# MRF39.net
KiCad netlist of a schematic drawn in EAGLE
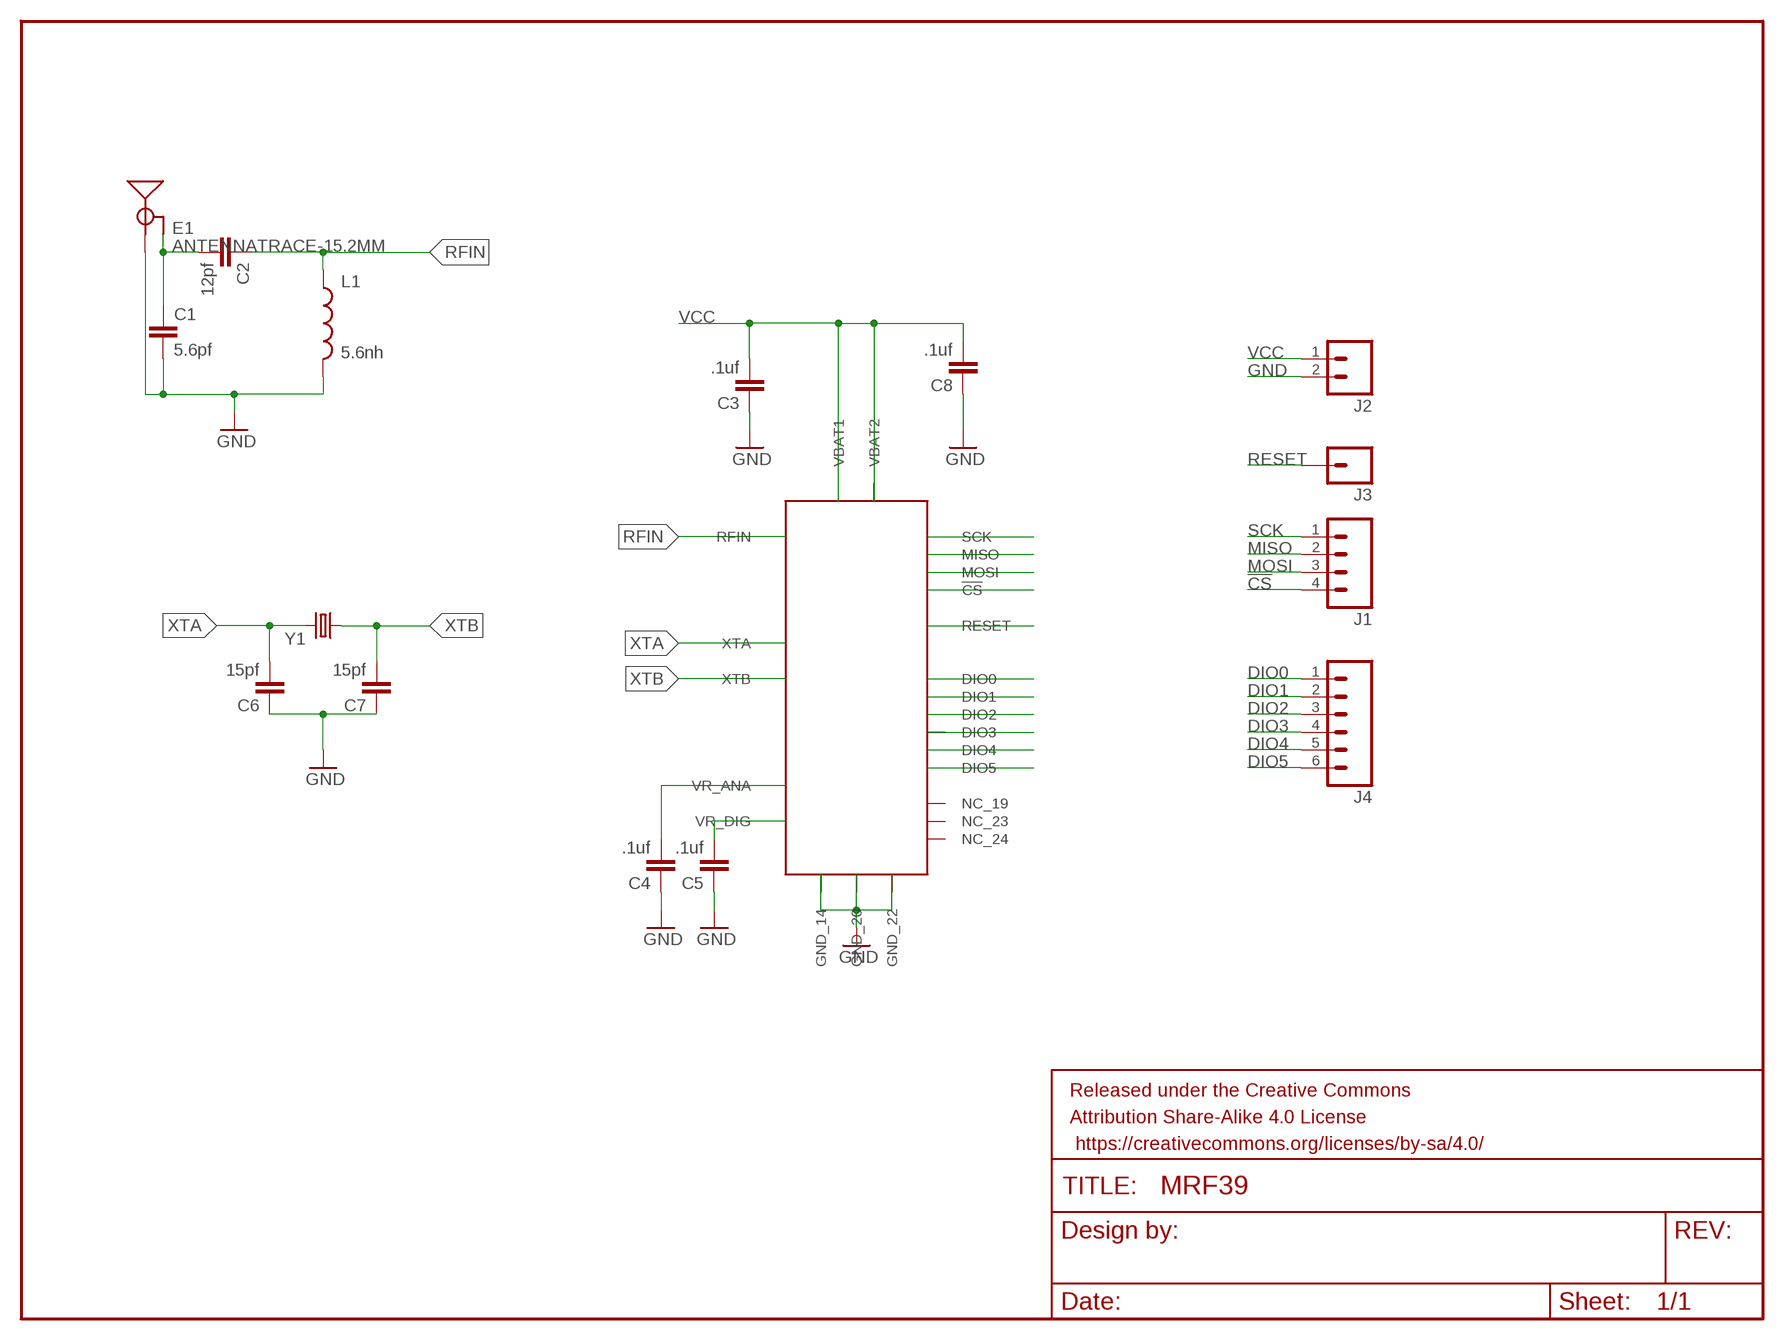
[diagram p0: schematic, sheet 1]

(export (version "E")
  (design (tool "Eeschema 10.0.6"))
  (components
    (comp (ref "C1")
      (value "5.6pf")
      (footprint "eagle-import:0603-CAP")
      (libsource (lib "eagle-import") (part "CAP0603-CAP"))
    )
    (comp (ref "C2")
      (value "12pf")
      (footprint "eagle-import:0603-CAP")
      (libsource (lib "eagle-import") (part "CAP0603-CAP"))
    )
    (comp (ref "C3")
      (value ".1uf")
      (footprint "eagle-import:0603-CAP")
      (libsource (lib "eagle-import") (part "CAP0603-CAP"))
    )
    (comp (ref "C4")
      (value ".1uf")
      (footprint "eagle-import:0603-CAP")
      (libsource (lib "eagle-import") (part "CAP0603-CAP"))
    )
    (comp (ref "C5")
      (value ".1uf")
      (footprint "eagle-import:0603-CAP")
      (libsource (lib "eagle-import") (part "CAP0603-CAP"))
    )
    (comp (ref "C6")
      (value "15pf")
      (footprint "eagle-import:0603-CAP")
      (libsource (lib "eagle-import") (part "CAP0603-CAP"))
    )
    (comp (ref "C7")
      (value "15pf")
      (footprint "eagle-import:0603-CAP")
      (libsource (lib "eagle-import") (part "CAP0603-CAP"))
    )
    (comp (ref "C8")
      (value ".1uf")
      (footprint "eagle-import:0603-CAP")
      (libsource (lib "eagle-import") (part "CAP0603-CAP"))
    )
    (comp (ref "E1")
      (value "ANTENNATRACE-15.2MM")
      (footprint "eagle-import:TRACE_ANTENNA_2.4GHZ_15.2MM")
      (libsource (lib "eagle-import") (part "ANTENNATRACE-15.2MM"))
    )
    (comp (ref "FRAME1")
      (value "FRAME-LETTERNO_PACKAGE")
      (footprint "eagle-import:DUMMY")
      (fields (field (name "DESIGNER") "Nobody"))
      (libsource (lib "eagle-import") (part "FRAME-LETTERNO_PACKAGE"))
    )
    (comp (ref "J1")
      (value "M04PTH")
      (footprint "eagle-import:1X04")
      (libsource (lib "eagle-import") (part "M04PTH"))
    )
    (comp (ref "J2")
      (value "M02PTH")
      (footprint "eagle-import:1X02")
      (libsource (lib "eagle-import") (part "M02PTH"))
    )
    (comp (ref "J3")
      (value "M01PTH")
      (footprint "eagle-import:1X01")
      (libsource (lib "eagle-import") (part "M01PTH"))
    )
    (comp (ref "J4")
      (value "M06SILK_FEMALE_PTH")
      (footprint "eagle-import:1X06")
      (libsource (lib "eagle-import") (part "M06SILK_FEMALE_PTH"))
    )
    (comp (ref "L1")
      (value "5.6nh")
      (footprint "eagle-import:0805")
      (libsource (lib "eagle-import") (part "INDUCTOR0805"))
    )
    (comp (ref "U1")
      (value "MRF39RATQFN24")
      (footprint "eagle-import:QFN24-5X5X1.0")
      (libsource (lib "eagle-import") (part "MRF39RATQFN24"))
    )
    (comp (ref "Y1")
      (value "CRYSTALSMD")
      (footprint "eagle-import:HC49UP")
      (libsource (lib "eagle-import") (part "CRYSTALSMD"))
    )
  )
  (nets
    (net (code "1") (name "/DIO0") (class "Default")
      (node (ref "J4") (pin "1") (pinfunction "1_1") (pintype "passive"))
      (node (ref "U1") (pin "7") (pinfunction "DIO0_7") (pintype "bidirectional"))
    )
    (net (code "2") (name "/DIO1") (class "Default")
      (node (ref "J4") (pin "2") (pinfunction "2_2") (pintype "passive"))
      (node (ref "U1") (pin "8") (pinfunction "DIO1_8") (pintype "bidirectional"))
    )
    (net (code "3") (name "/DIO2") (class "Default")
      (node (ref "J4") (pin "3") (pinfunction "3_3") (pintype "passive"))
      (node (ref "U1") (pin "9") (pinfunction "DIO2_9") (pintype "bidirectional"))
    )
    (net (code "4") (name "/DIO3") (class "Default")
      (node (ref "J4") (pin "4") (pinfunction "4_4") (pintype "passive"))
      (node (ref "U1") (pin "10") (pinfunction "DIO3_10") (pintype "bidirectional"))
    )
    (net (code "5") (name "/DIO4") (class "Default")
      (node (ref "J4") (pin "5") (pinfunction "5_5") (pintype "passive"))
      (node (ref "U1") (pin "11") (pinfunction "DIO4_11") (pintype "bidirectional"))
    )
    (net (code "6") (name "/DIO5") (class "Default")
      (node (ref "J4") (pin "6") (pinfunction "6_6") (pintype "passive"))
      (node (ref "U1") (pin "12") (pinfunction "DIO5_12") (pintype "bidirectional"))
    )
    (net (code "7") (name "/MISO") (class "Default")
      (node (ref "J1") (pin "2") (pinfunction "2_2") (pintype "passive"))
      (node (ref "U1") (pin "16") (pinfunction "MISO_16") (pintype "bidirectional"))
    )
    (net (code "8") (name "/MOSI") (class "Default")
      (node (ref "J1") (pin "3") (pinfunction "3_3") (pintype "passive"))
      (node (ref "U1") (pin "17") (pinfunction "MOSI_17") (pintype "bidirectional"))
    )
    (net (code "9") (name "/RESET") (class "Default")
      (node (ref "J3") (pin "1") (pinfunction "1_1") (pintype "passive"))
      (node (ref "U1") (pin "6") (pinfunction "RESET_6") (pintype "bidirectional"))
    )
    (net (code "10") (name "/SCK") (class "Default")
      (node (ref "J1") (pin "1") (pinfunction "1_1") (pintype "passive"))
      (node (ref "U1") (pin "15") (pinfunction "SCK_15") (pintype "bidirectional"))
    )
    (net (code "11") (name "/VCC") (class "Default")
      (node (ref "C3") (pin "2") (pinfunction "2_2") (pintype "passive"))
      (node (ref "C8") (pin "2") (pinfunction "2_2") (pintype "passive"))
      (node (ref "J2") (pin "1") (pinfunction "1_1") (pintype "passive"))
      (node (ref "U1") (pin "1") (pinfunction "VBAT1_1") (pintype "bidirectional"))
      (node (ref "U1") (pin "13") (pinfunction "VBAT2_13") (pintype "bidirectional"))
    )
    (net (code "12") (name "/~{CS}") (class "Default")
      (node (ref "J1") (pin "4") (pinfunction "4_4") (pintype "passive"))
      (node (ref "U1") (pin "18") (pinfunction "~{CS}_18") (pintype "bidirectional"))
    )
    (net (code "13") (name "GND") (class "Default")
      (node (ref "C1") (pin "2") (pinfunction "2_2") (pintype "passive"))
      (node (ref "C3") (pin "1") (pinfunction "1_1") (pintype "passive"))
      (node (ref "C4") (pin "1") (pinfunction "1_1") (pintype "passive"))
      (node (ref "C5") (pin "1") (pinfunction "1_1") (pintype "passive"))
      (node (ref "C6") (pin "1") (pinfunction "1_1") (pintype "passive"))
      (node (ref "C7") (pin "1") (pinfunction "1_1") (pintype "passive"))
      (node (ref "C8") (pin "1") (pinfunction "1_1") (pintype "passive"))
      (node (ref "E1") (pin "ANT") (pinfunction "SIGNAL_ANT") (pintype "bidirectional"))
      (node (ref "J2") (pin "2") (pinfunction "2_2") (pintype "passive"))
      (node (ref "L1") (pin "2") (pinfunction "2_2") (pintype "passive"))
      (node (ref "U1") (pin "14") (pinfunction "GND_14_14") (pintype "power_in"))
      (node (ref "U1") (pin "20") (pinfunction "GND_20_20") (pintype "power_in"))
      (node (ref "U1") (pin "22") (pinfunction "GND_22_22") (pintype "power_in"))
    )
    (net (code "14") (name "Net-(C1-Pad1)") (class "Default")
      (node (ref "C1") (pin "1") (pinfunction "1_1") (pintype "passive"))
      (node (ref "C2") (pin "2") (pinfunction "2_2") (pintype "passive"))
      (node (ref "E1") (pin "GND") (pinfunction "GND_GND") (pintype "bidirectional"))
    )
    (net (code "15") (name "Net-(U1-VR_ANA)") (class "Default")
      (node (ref "C4") (pin "2") (pinfunction "2_2") (pintype "passive"))
      (node (ref "U1") (pin "2") (pinfunction "VR_ANA_2") (pintype "power_in"))
    )
    (net (code "16") (name "Net-(U1-VR_DIG)") (class "Default")
      (node (ref "C5") (pin "2") (pinfunction "2_2") (pintype "passive"))
      (node (ref "U1") (pin "3") (pinfunction "VR_DIG_3") (pintype "power_in"))
    )
    (net (code "17") (name "RFIN") (class "Default")
      (node (ref "C2") (pin "1") (pinfunction "1_1") (pintype "passive"))
      (node (ref "L1") (pin "1") (pinfunction "1_1") (pintype "passive"))
      (node (ref "U1") (pin "21") (pinfunction "RFIN_21") (pintype "output"))
    )
    (net (code "18") (name "XTA") (class "Default")
      (node (ref "C6") (pin "2") (pinfunction "2_2") (pintype "passive"))
      (node (ref "U1") (pin "4") (pinfunction "XTA_4") (pintype "power_in"))
      (node (ref "Y1") (pin "2") (pinfunction "2_2") (pintype "passive"))
    )
    (net (code "19") (name "XTB") (class "Default")
      (node (ref "C7") (pin "2") (pinfunction "2_2") (pintype "passive"))
      (node (ref "U1") (pin "5") (pinfunction "XTB_5") (pintype "power_in"))
      (node (ref "Y1") (pin "1") (pinfunction "1_1") (pintype "passive"))
    )
    (net (code "20") (name "unconnected-(U1-NC_19-Pad19)") (class "Default")
      (node (ref "U1") (pin "19") (pinfunction "NC_19_19") (pintype "no_connect"))
    )
    (net (code "21") (name "unconnected-(U1-NC_23-Pad23)") (class "Default")
      (node (ref "U1") (pin "23") (pinfunction "NC_23_23") (pintype "no_connect"))
    )
    (net (code "22") (name "unconnected-(U1-NC_24-Pad24)") (class "Default")
      (node (ref "U1") (pin "24") (pinfunction "NC_24_24") (pintype "no_connect"))
    )
  )
)
